# 2025-02-19_audio_board.net
KiCad netlist of a schematic drawn in EAGLE
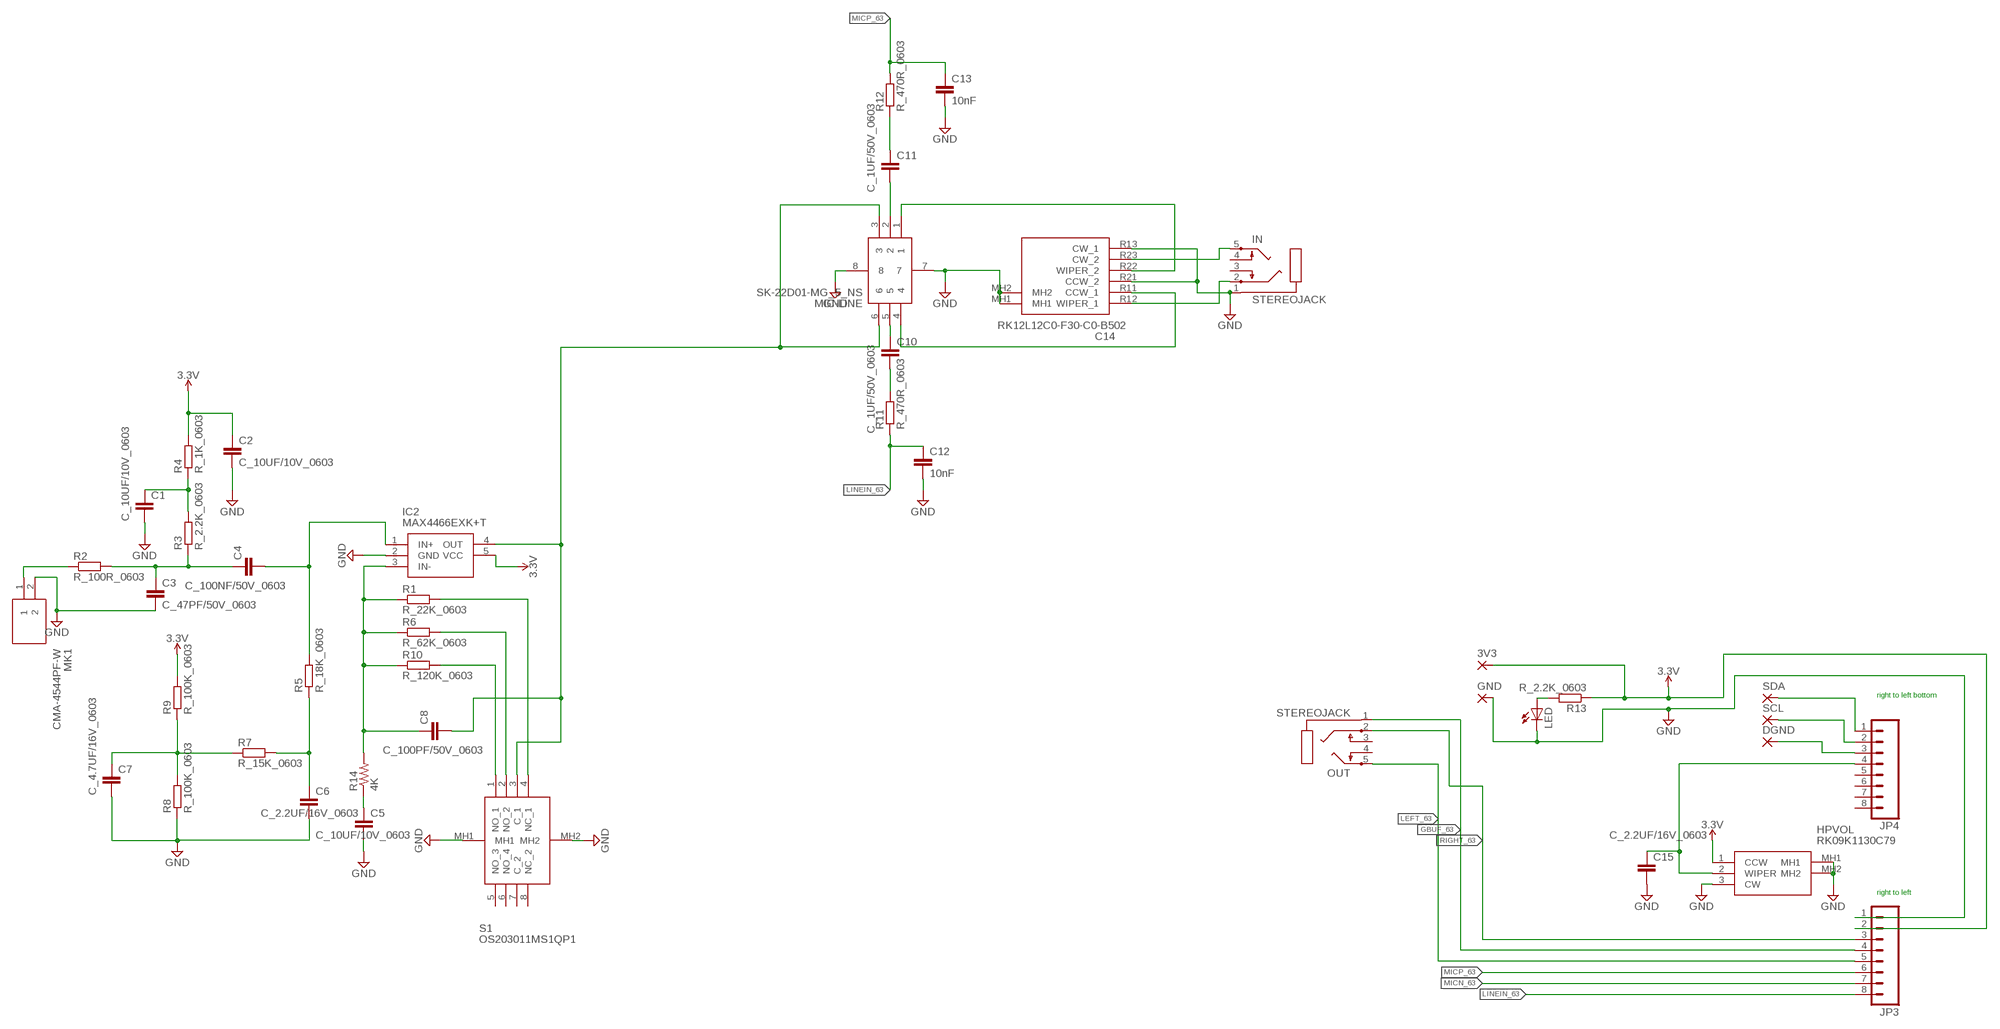
[diagram p0: schematic, sheet 1]

(export (version "E")
  (design (tool "Eeschema 10.0.6"))
  (components
    (comp (ref "3V3")
      (value "2,54/1,0")
      (footprint "eagle-import:2,54_1,0")
      (libsource (lib "eagle-import") (part "2,54/1,0"))
    )
    (comp (ref "C1")
      (value "C_10UF/10V_0603")
      (footprint "eagle-import:C0603")
      (fields (field (name "LCSC_PART") "C19702"))
      (libsource (lib "eagle-import") (part "C__060310UF/10V"))
    )
    (comp (ref "C2")
      (value "C_10UF/10V_0603")
      (footprint "eagle-import:C0603")
      (fields (field (name "LCSC_PART") "C19702"))
      (libsource (lib "eagle-import") (part "C__060310UF/10V"))
    )
    (comp (ref "C3")
      (value "C_47PF/50V_0603")
      (footprint "eagle-import:C0603")
      (fields (field (name "LCSC_PART") "C1671"))
      (libsource (lib "eagle-import") (part "C__060347PF/50V"))
    )
    (comp (ref "C4")
      (value "C_100NF/50V_0603")
      (footprint "eagle-import:C0603")
      (fields (field (name "LCSC_PART") "C14663"))
      (libsource (lib "eagle-import") (part "C__0603100NF/50V"))
    )
    (comp (ref "C5")
      (value "C_10UF/10V_0603")
      (footprint "eagle-import:C0603")
      (fields (field (name "LCSC_PART") "C19702"))
      (libsource (lib "eagle-import") (part "C__060310UF/10V"))
    )
    (comp (ref "C6")
      (value "C_2.2UF/16V_0603")
      (footprint "eagle-import:C0603")
      (fields (field (name "LCSC_PART") "C23630"))
      (libsource (lib "eagle-import") (part "C__06032.2UF/16V"))
    )
    (comp (ref "C7")
      (value "C_4.7UF/16V_0603")
      (footprint "eagle-import:C0603")
      (fields (field (name "LCSC_PART") "C19666"))
      (libsource (lib "eagle-import") (part "C__06034.7UF/16V"))
    )
    (comp (ref "C8")
      (value "C_100PF/50V_0603")
      (footprint "eagle-import:C0603")
      (fields (field (name "LCSC_PART") "C14858"))
      (libsource (lib "eagle-import") (part "C__0603100PF/50V"))
    )
    (comp (ref "C10")
      (value "C_1UF/50V_0603")
      (footprint "eagle-import:C0603")
      (fields (field (name "LCSC_PART") "C15849"))
      (libsource (lib "eagle-import") (part "C__06031UF/50V"))
    )
    (comp (ref "C11")
      (value "C_1UF/50V_0603")
      (footprint "eagle-import:C0603")
      (fields (field (name "LCSC_PART") "C15849"))
      (libsource (lib "eagle-import") (part "C__06031UF/50V"))
    )
    (comp (ref "C12")
      (value "10nF")
      (footprint "eagle-import:0603")
      (libsource (lib "eagle-import") (part "10NF-0603-50V-10%"))
    )
    (comp (ref "C13")
      (value "10nF")
      (footprint "eagle-import:0603")
      (libsource (lib "eagle-import") (part "10NF-0603-50V-10%"))
    )
    (comp (ref "C14")
      (value "RK12L12C0-F30-C0-B502")
      (footprint "eagle-import:RK12L12C0F30C0B502")
      (libsource (lib "eagle-import") (part "RK12L12C0-F30-C0-B502"))
    )
    (comp (ref "C15")
      (value "C_2.2UF/16V_0603")
      (footprint "eagle-import:C0603")
      (fields (field (name "LCSC_PART") "C23630"))
      (libsource (lib "eagle-import") (part "C__06032.2UF/16V"))
    )
    (comp (ref "DGND")
      (value "2,54/1,0")
      (footprint "eagle-import:2,54_1,0")
      (libsource (lib "eagle-import") (part "2,54/1,0"))
    )
    (comp (ref "GND")
      (value "2,54/1,0")
      (footprint "eagle-import:2,54_1,0")
      (libsource (lib "eagle-import") (part "2,54/1,0"))
    )
    (comp (ref "HPVOL")
      (value "RK09K1130C79")
      (footprint "eagle-import:RK09K1130C79")
      (libsource (lib "eagle-import") (part "RK09K1130C79"))
    )
    (comp (ref "IC2")
      (value "MAX4466EXK+T")
      (footprint "eagle-import:SOT65P210X110-5N")
      (fields (field (name "MOUSER_PART_NUMBER") "700-MAX4466EXKT"))
      (libsource (lib "eagle-import") (part "MAX4466EXK+T"))
    )
    (comp (ref "IN")
      (value "STEREOJACK")
      (footprint "eagle-import:STX3100")
      (libsource (lib "eagle-import") (part "STEREOJACK"))
    )
    (comp (ref "JP3")
      (value "M08")
      (footprint "eagle-import:1X08_ROUND")
      (libsource (lib "eagle-import") (part "M08"))
    )
    (comp (ref "JP4")
      (value "M08")
      (footprint "eagle-import:1X08_ROUND")
      (libsource (lib "eagle-import") (part "M08"))
    )
    (comp (ref "LED")
      (value "LED")
      (footprint "eagle-import:SMARTLED-TTW")
      (libsource (lib "eagle-import") (part "LED"))
    )
    (comp (ref "MIC-LINE")
      (value "SK-22D01-MG_5_NS")
      (footprint "eagle-import:SK22D01MG5NS")
      (fields
        (field (name "ARROW_PART_NUMBER") "SK-22D01-MG 5 NS")
        (field (name "MOUSER_PART_NUMBER") "611-SK-22D01-MG5NS")
      )
      (libsource (lib "eagle-import") (part "SK-22D01-MG_5_NS"))
    )
    (comp (ref "MK1")
      (value "CMA-4544PF-W")
      (footprint "eagle-import:CMA4544PFW")
      (fields (field (name "MOUSER_PART_NUMBER") "490-CMA-4544PF-W"))
      (libsource (lib "eagle-import") (part "CMA-4544PF-W"))
    )
    (comp (ref "OUT")
      (value "STEREOJACK")
      (footprint "eagle-import:STX3100")
      (libsource (lib "eagle-import") (part "STEREOJACK"))
    )
    (comp (ref "R1")
      (value "R_22K_0603")
      (footprint "eagle-import:R0603")
      (fields (field (name "LCSC_PART") "C31850"))
      (libsource (lib "eagle-import") (part "R__060322K"))
    )
    (comp (ref "R2")
      (value "R_100R_0603")
      (footprint "eagle-import:R0603")
      (fields (field (name "LCSC_PART") "C22775"))
      (libsource (lib "eagle-import") (part "R__0603100R"))
    )
    (comp (ref "R3")
      (value "R_2.2K_0603")
      (footprint "eagle-import:R0603")
      (fields (field (name "LCSC_PART") "C4190"))
      (libsource (lib "eagle-import") (part "R__06032.2K"))
    )
    (comp (ref "R4")
      (value "R_1K_0603")
      (footprint "eagle-import:R0603")
      (fields (field (name "LCSC_PART") "C21190"))
      (libsource (lib "eagle-import") (part "R__06031K"))
    )
    (comp (ref "R5")
      (value "R_18K_0603")
      (footprint "eagle-import:R0603")
      (fields (field (name "LCSC_PART") "C25810"))
      (libsource (lib "eagle-import") (part "R__060318K"))
    )
    (comp (ref "R6")
      (value "R_62K_0603")
      (footprint "eagle-import:R0603")
      (fields (field (name "LCSC_PART") "C23221"))
      (libsource (lib "eagle-import") (part "R__060362K"))
    )
    (comp (ref "R7")
      (value "R_15K_0603")
      (footprint "eagle-import:R0603")
      (fields (field (name "LCSC_PART") "C22809"))
      (libsource (lib "eagle-import") (part "R__060315K"))
    )
    (comp (ref "R8")
      (value "R_100K_0603")
      (footprint "eagle-import:R0603")
      (fields (field (name "LCSC_PART") "C25803"))
      (libsource (lib "eagle-import") (part "R__0603100K"))
    )
    (comp (ref "R9")
      (value "R_100K_0603")
      (footprint "eagle-import:R0603")
      (fields (field (name "LCSC_PART") "C25803"))
      (libsource (lib "eagle-import") (part "R__0603100K"))
    )
    (comp (ref "R10")
      (value "R_120K_0603")
      (footprint "eagle-import:R0603")
      (fields (field (name "LCSC_PART") "C25808"))
      (libsource (lib "eagle-import") (part "R__0603120K"))
    )
    (comp (ref "R11")
      (value "R_470R_0603")
      (footprint "eagle-import:R0603")
      (fields (field (name "LCSC_PART") "C23179"))
      (libsource (lib "eagle-import") (part "R__0603470R"))
    )
    (comp (ref "R12")
      (value "R_470R_0603")
      (footprint "eagle-import:R0603")
      (fields (field (name "LCSC_PART") "C23179"))
      (libsource (lib "eagle-import") (part "R__0603470R"))
    )
    (comp (ref "R13")
      (value "R_2.2K_0603")
      (footprint "eagle-import:R0603")
      (fields (field (name "LCSC_PART") "C4190"))
      (libsource (lib "eagle-import") (part "R__06032.2K"))
    )
    (comp (ref "R14")
      (value "4K")
      (footprint "eagle-import:R0603")
      (libsource (lib "eagle-import") (part "R-US_R0603"))
    )
    (comp (ref "S1")
      (value "OS203011MS1QP1")
      (footprint "eagle-import:OS203011MS1QP1")
      (fields (field (name "MOUSER_PART_NUMBER") "611-OS203011MS1QP1"))
      (libsource (lib "eagle-import") (part "OS203011MS1QP1"))
    )
    (comp (ref "SCL")
      (value "2,54/1,0")
      (footprint "eagle-import:2,54_1,0")
      (libsource (lib "eagle-import") (part "2,54/1,0"))
    )
    (comp (ref "SDA")
      (value "2,54/1,0")
      (footprint "eagle-import:2,54_1,0")
      (libsource (lib "eagle-import") (part "2,54/1,0"))
    )
  )
  (nets
    (net (code "1") (name "3.3V") (class "Default")
      (node (ref "3V3") (pin "1") (pinfunction "P_1") (pintype "passive"))
      (node (ref "C2") (pin "1") (pinfunction "1_1") (pintype "passive"))
      (node (ref "HPVOL") (pin "1") (pinfunction "CCW_1") (pintype "bidirectional"))
      (node (ref "IC2") (pin "5") (pinfunction "VCC_5") (pintype "bidirectional"))
      (node (ref "JP3") (pin "2") (pinfunction "2_2") (pintype "passive"))
      (node (ref "R13") (pin "1") (pinfunction "1_1") (pintype "passive"))
      (node (ref "R4") (pin "2") (pinfunction "2_2") (pintype "passive"))
      (node (ref "R9") (pin "2") (pinfunction "2_2") (pintype "passive"))
    )
    (net (code "2") (name "GBUF_63") (class "Default")
      (node (ref "JP3") (pin "4") (pinfunction "4_4") (pintype "passive"))
      (node (ref "OUT") (pin "1") (pinfunction "1_1") (pintype "passive"))
    )
    (net (code "3") (name "GND") (class "Default")
      (node (ref "C1") (pin "2") (pinfunction "2_2") (pintype "passive"))
      (node (ref "C12") (pin "2") (pinfunction "2_2") (pintype "passive"))
      (node (ref "C13") (pin "2") (pinfunction "2_2") (pintype "passive"))
      (node (ref "C14") (pin "MH1") (pinfunction "MH1_MH1") (pintype "bidirectional"))
      (node (ref "C14") (pin "MH2") (pinfunction "MH2_MH2") (pintype "bidirectional"))
      (node (ref "C14") (pin "R13") (pinfunction "CW_1_R13") (pintype "bidirectional"))
      (node (ref "C14") (pin "R21") (pinfunction "CCW_2_R21") (pintype "bidirectional"))
      (node (ref "C15") (pin "2") (pinfunction "2_2") (pintype "passive"))
      (node (ref "C2") (pin "2") (pinfunction "2_2") (pintype "passive"))
      (node (ref "C3") (pin "2") (pinfunction "2_2") (pintype "passive"))
      (node (ref "C5") (pin "2") (pinfunction "2_2") (pintype "passive"))
      (node (ref "C6") (pin "2") (pinfunction "2_2") (pintype "passive"))
      (node (ref "C7") (pin "2") (pinfunction "2_2") (pintype "passive"))
      (node (ref "GND") (pin "1") (pinfunction "P_1") (pintype "passive"))
      (node (ref "HPVOL") (pin "3") (pinfunction "CW_3") (pintype "bidirectional"))
      (node (ref "HPVOL") (pin "MH1") (pinfunction "MH1_MH1") (pintype "bidirectional"))
      (node (ref "HPVOL") (pin "MH2") (pinfunction "MH2_MH2") (pintype "bidirectional"))
      (node (ref "IC2") (pin "2") (pinfunction "GND_2") (pintype "bidirectional"))
      (node (ref "IN") (pin "1") (pinfunction "1_1") (pintype "passive"))
      (node (ref "JP3") (pin "1") (pinfunction "1_1") (pintype "passive"))
      (node (ref "LED") (pin "C@1") (pinfunction "C_C@1") (pintype "passive"))
      (node (ref "MIC-LINE") (pin "7") (pinfunction "7_7") (pintype "bidirectional"))
      (node (ref "MIC-LINE") (pin "8") (pinfunction "8_8") (pintype "bidirectional"))
      (node (ref "MK1") (pin "2") (pinfunction "2_2") (pintype "bidirectional"))
      (node (ref "R8") (pin "1") (pinfunction "1_1") (pintype "passive"))
      (node (ref "S1") (pin "MH1") (pinfunction "MH1_MH1") (pintype "bidirectional"))
      (node (ref "S1") (pin "MH2") (pinfunction "MH2_MH2") (pintype "bidirectional"))
    )
    (net (code "4") (name "LEFT_63") (class "Default")
      (node (ref "JP3") (pin "5") (pinfunction "5_5") (pintype "passive"))
      (node (ref "OUT") (pin "5") (pinfunction "5_5") (pintype "passive"))
    )
    (net (code "5") (name "LINEIN_63") (class "Default")
      (node (ref "C12") (pin "1") (pinfunction "1_1") (pintype "passive"))
      (node (ref "JP3") (pin "8") (pinfunction "8_8") (pintype "passive"))
      (node (ref "R11") (pin "1") (pinfunction "1_1") (pintype "passive"))
    )
    (net (code "6") (name "MICN_63") (class "Default")
      (node (ref "JP3") (pin "7") (pinfunction "7_7") (pintype "passive"))
    )
    (net (code "7") (name "MICP_63") (class "Default")
      (node (ref "C13") (pin "1") (pinfunction "1_1") (pintype "passive"))
      (node (ref "JP3") (pin "6") (pinfunction "6_6") (pintype "passive"))
      (node (ref "R12") (pin "2") (pinfunction "2_2") (pintype "passive"))
    )
    (net (code "8") (name "Net-(C1-Pad1)") (class "Default")
      (node (ref "C1") (pin "1") (pinfunction "1_1") (pintype "passive"))
      (node (ref "R3") (pin "2") (pinfunction "2_2") (pintype "passive"))
      (node (ref "R4") (pin "1") (pinfunction "1_1") (pintype "passive"))
    )
    (net (code "9") (name "Net-(C3-Pad1)") (class "Default")
      (node (ref "C3") (pin "1") (pinfunction "1_1") (pintype "passive"))
      (node (ref "C4") (pin "1") (pinfunction "1_1") (pintype "passive"))
      (node (ref "R2") (pin "2") (pinfunction "2_2") (pintype "passive"))
      (node (ref "R3") (pin "1") (pinfunction "1_1") (pintype "passive"))
    )
    (net (code "10") (name "Net-(C5-Pad1)") (class "Default")
      (node (ref "C5") (pin "1") (pinfunction "1_1") (pintype "passive"))
      (node (ref "R14") (pin "1") (pinfunction "1_1") (pintype "passive"))
    )
    (net (code "11") (name "Net-(C6-Pad1)") (class "Default")
      (node (ref "C6") (pin "1") (pinfunction "1_1") (pintype "passive"))
      (node (ref "R5") (pin "1") (pinfunction "1_1") (pintype "passive"))
      (node (ref "R7") (pin "2") (pinfunction "2_2") (pintype "passive"))
    )
    (net (code "12") (name "Net-(C7-Pad1)") (class "Default")
      (node (ref "C7") (pin "1") (pinfunction "1_1") (pintype "passive"))
      (node (ref "R7") (pin "1") (pinfunction "1_1") (pintype "passive"))
      (node (ref "R8") (pin "2") (pinfunction "2_2") (pintype "passive"))
      (node (ref "R9") (pin "1") (pinfunction "1_1") (pintype "passive"))
    )
    (net (code "13") (name "Net-(C10-Pad1)") (class "Default")
      (node (ref "C10") (pin "1") (pinfunction "1_1") (pintype "passive"))
      (node (ref "MIC-LINE") (pin "5") (pinfunction "5_5") (pintype "bidirectional"))
    )
    (net (code "14") (name "Net-(C10-Pad2)") (class "Default")
      (node (ref "C10") (pin "2") (pinfunction "2_2") (pintype "passive"))
      (node (ref "R11") (pin "2") (pinfunction "2_2") (pintype "passive"))
    )
    (net (code "15") (name "Net-(C11-Pad1)") (class "Default")
      (node (ref "C11") (pin "1") (pinfunction "1_1") (pintype "passive"))
      (node (ref "R12") (pin "1") (pinfunction "1_1") (pintype "passive"))
    )
    (net (code "16") (name "Net-(C11-Pad2)") (class "Default")
      (node (ref "C11") (pin "2") (pinfunction "2_2") (pintype "passive"))
      (node (ref "MIC-LINE") (pin "2") (pinfunction "2_2") (pintype "bidirectional"))
    )
    (net (code "17") (name "Net-(C14-CCW_1)") (class "Default")
      (node (ref "C14") (pin "R11") (pinfunction "CCW_1_R11") (pintype "bidirectional"))
      (node (ref "MIC-LINE") (pin "4") (pinfunction "4_4") (pintype "bidirectional"))
    )
    (net (code "18") (name "Net-(C14-CW_2)") (class "Default")
      (node (ref "C14") (pin "R23") (pinfunction "CW_2_R23") (pintype "bidirectional"))
      (node (ref "IN") (pin "5") (pinfunction "5_5") (pintype "passive"))
    )
    (net (code "19") (name "Net-(C14-WIPER_1)") (class "Default")
      (node (ref "C14") (pin "R12") (pinfunction "WIPER_1_R12") (pintype "bidirectional"))
      (node (ref "IN") (pin "2") (pinfunction "2_2") (pintype "passive"))
    )
    (net (code "20") (name "Net-(C14-WIPER_2)") (class "Default")
      (node (ref "C14") (pin "R22") (pinfunction "WIPER_2_R22") (pintype "bidirectional"))
      (node (ref "MIC-LINE") (pin "1") (pinfunction "1_1") (pintype "bidirectional"))
    )
    (net (code "21") (name "Net-(DGND-P)") (class "Default")
      (node (ref "DGND") (pin "1") (pinfunction "P_1") (pintype "passive"))
      (node (ref "JP4") (pin "3") (pinfunction "3_3") (pintype "passive"))
    )
    (net (code "22") (name "Net-(HPVOL-WIPER)") (class "Default")
      (node (ref "C15") (pin "1") (pinfunction "1_1") (pintype "passive"))
      (node (ref "HPVOL") (pin "2") (pinfunction "WIPER_2") (pintype "bidirectional"))
      (node (ref "JP4") (pin "4") (pinfunction "4_4") (pintype "passive"))
    )
    (net (code "23") (name "Net-(IC2-IN+)") (class "Default")
      (node (ref "C4") (pin "2") (pinfunction "2_2") (pintype "passive"))
      (node (ref "IC2") (pin "1") (pinfunction "IN+_1") (pintype "bidirectional"))
      (node (ref "R5") (pin "2") (pinfunction "2_2") (pintype "passive"))
    )
    (net (code "24") (name "Net-(IC2-IN-)") (class "Default")
      (node (ref "C8") (pin "1") (pinfunction "1_1") (pintype "passive"))
      (node (ref "IC2") (pin "3") (pinfunction "IN-_3") (pintype "bidirectional"))
      (node (ref "R1") (pin "1") (pinfunction "1_1") (pintype "passive"))
      (node (ref "R10") (pin "1") (pinfunction "1_1") (pintype "passive"))
      (node (ref "R14") (pin "2") (pinfunction "2_2") (pintype "passive"))
      (node (ref "R6") (pin "1") (pinfunction "1_1") (pintype "passive"))
    )
    (net (code "25") (name "Net-(IC2-OUT)") (class "Default")
      (node (ref "C8") (pin "2") (pinfunction "2_2") (pintype "passive"))
      (node (ref "IC2") (pin "4") (pinfunction "OUT_4") (pintype "bidirectional"))
      (node (ref "MIC-LINE") (pin "3") (pinfunction "3_3") (pintype "bidirectional"))
      (node (ref "MIC-LINE") (pin "6") (pinfunction "6_6") (pintype "bidirectional"))
      (node (ref "S1") (pin "3") (pinfunction "C_1_3") (pintype "bidirectional"))
    )
    (net (code "26") (name "Net-(LED-A)") (class "Default")
      (node (ref "LED") (pin "A@1") (pinfunction "A_A@1") (pintype "passive"))
      (node (ref "R13") (pin "2") (pinfunction "2_2") (pintype "passive"))
    )
    (net (code "27") (name "Net-(MK1-Pad1)") (class "Default")
      (node (ref "MK1") (pin "1") (pinfunction "1_1") (pintype "bidirectional"))
      (node (ref "R2") (pin "1") (pinfunction "1_1") (pintype "passive"))
    )
    (net (code "28") (name "Net-(S1-NC_1)") (class "Default")
      (node (ref "R1") (pin "2") (pinfunction "2_2") (pintype "passive"))
      (node (ref "S1") (pin "4") (pinfunction "NC_1_4") (pintype "bidirectional"))
    )
    (net (code "29") (name "Net-(S1-NO_1)") (class "Default")
      (node (ref "R10") (pin "2") (pinfunction "2_2") (pintype "passive"))
      (node (ref "S1") (pin "1") (pinfunction "NO_1_1") (pintype "bidirectional"))
    )
    (net (code "30") (name "Net-(S1-NO_2)") (class "Default")
      (node (ref "R6") (pin "2") (pinfunction "2_2") (pintype "passive"))
      (node (ref "S1") (pin "2") (pinfunction "NO_2_2") (pintype "bidirectional"))
    )
    (net (code "31") (name "Net-(SCL-P)") (class "Default")
      (node (ref "JP4") (pin "2") (pinfunction "2_2") (pintype "passive"))
      (node (ref "SCL") (pin "1") (pinfunction "P_1") (pintype "passive"))
    )
    (net (code "32") (name "Net-(SDA-P)") (class "Default")
      (node (ref "JP4") (pin "1") (pinfunction "1_1") (pintype "passive"))
      (node (ref "SDA") (pin "1") (pinfunction "P_1") (pintype "passive"))
    )
    (net (code "33") (name "RIGHT_63") (class "Default")
      (node (ref "JP3") (pin "3") (pinfunction "3_3") (pintype "passive"))
      (node (ref "OUT") (pin "2") (pinfunction "2_2") (pintype "passive"))
    )
    (net (code "34") (name "unconnected-(IN-Pad3)") (class "Default")
      (node (ref "IN") (pin "3") (pinfunction "3_3") (pintype "passive"))
    )
    (net (code "35") (name "unconnected-(IN-Pad4)") (class "Default")
      (node (ref "IN") (pin "4") (pinfunction "4_4") (pintype "passive"))
    )
    (net (code "36") (name "unconnected-(JP4-Pad5)") (class "Default")
      (node (ref "JP4") (pin "5") (pinfunction "5_5") (pintype "passive"))
    )
    (net (code "37") (name "unconnected-(JP4-Pad6)") (class "Default")
      (node (ref "JP4") (pin "6") (pinfunction "6_6") (pintype "passive"))
    )
    (net (code "38") (name "unconnected-(JP4-Pad7)") (class "Default")
      (node (ref "JP4") (pin "7") (pinfunction "7_7") (pintype "passive"))
    )
    (net (code "39") (name "unconnected-(JP4-Pad8)") (class "Default")
      (node (ref "JP4") (pin "8") (pinfunction "8_8") (pintype "passive"))
    )
    (net (code "40") (name "unconnected-(OUT-Pad3)") (class "Default")
      (node (ref "OUT") (pin "3") (pinfunction "3_3") (pintype "passive"))
    )
    (net (code "41") (name "unconnected-(OUT-Pad4)") (class "Default")
      (node (ref "OUT") (pin "4") (pinfunction "4_4") (pintype "passive"))
    )
    (net (code "42") (name "unconnected-(S1-C_2-Pad7)") (class "Default")
      (node (ref "S1") (pin "7") (pinfunction "C_2_7") (pintype "bidirectional"))
    )
    (net (code "43") (name "unconnected-(S1-NC_2-Pad8)") (class "Default")
      (node (ref "S1") (pin "8") (pinfunction "NC_2_8") (pintype "bidirectional"))
    )
    (net (code "44") (name "unconnected-(S1-NO_3-Pad5)") (class "Default")
      (node (ref "S1") (pin "5") (pinfunction "NO_3_5") (pintype "bidirectional"))
    )
    (net (code "45") (name "unconnected-(S1-NO_4-Pad6)") (class "Default")
      (node (ref "S1") (pin "6") (pinfunction "NO_4_6") (pintype "bidirectional"))
    )
  )
)
